# AV-DC.net
KiCad netlist of a schematic drawn in EAGLE
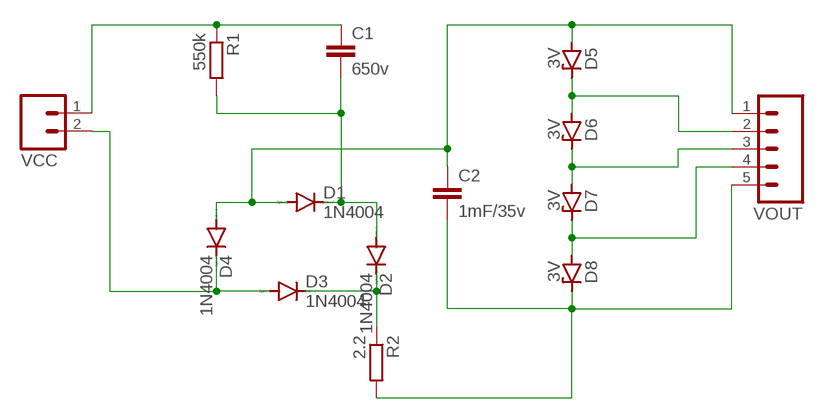
[diagram p0: schematic, sheet 1]

(export (version "E")
  (design (tool "Eeschema 10.0.6"))
  (components
    (comp (ref "C1")
      (value "650v")
      (footprint "eagle-import:C5B3")
      (libsource (lib "eagle-import") (part "C5/3"))
    )
    (comp (ref "C2")
      (value "1mF/35v")
      (footprint "eagle-import:C2.5-2")
      (libsource (lib "eagle-import") (part "C2.5/2"))
    )
    (comp (ref "D1")
      (value "1N4004")
      (footprint "eagle-import:DO41-10")
      (libsource (lib "eagle-import") (part "1N4004"))
    )
    (comp (ref "D2")
      (value "1N4004")
      (footprint "eagle-import:DO41-10")
      (libsource (lib "eagle-import") (part "1N4004"))
    )
    (comp (ref "D3")
      (value "1N4004")
      (footprint "eagle-import:DO41-10")
      (libsource (lib "eagle-import") (part "1N4004"))
    )
    (comp (ref "D4")
      (value "1N4004")
      (footprint "eagle-import:DO41-10")
      (libsource (lib "eagle-import") (part "1N4004"))
    )
    (comp (ref "D5")
      (value "3V")
      (footprint "eagle-import:DO41Z10")
      (libsource (lib "eagle-import") (part "ZENER-DIODEDO41Z10"))
    )
    (comp (ref "D6")
      (value "3V")
      (footprint "eagle-import:DO41Z10")
      (libsource (lib "eagle-import") (part "ZENER-DIODEDO41Z10"))
    )
    (comp (ref "D7")
      (value "3V")
      (footprint "eagle-import:DO41Z10")
      (libsource (lib "eagle-import") (part "ZENER-DIODEDO41Z10"))
    )
    (comp (ref "D8")
      (value "3V")
      (footprint "eagle-import:DO41Z10")
      (libsource (lib "eagle-import") (part "ZENER-DIODEDO41Z10"))
    )
    (comp (ref "R1")
      (value "550k")
      (footprint "eagle-import:0207_10")
      (libsource (lib "eagle-import") (part "R-EU_0207/10"))
    )
    (comp (ref "R2")
      (value "2.2")
      (footprint "eagle-import:0207_10")
      (libsource (lib "eagle-import") (part "R-EU_0207/10"))
    )
    (comp (ref "VCC")
      (value "M02")
      (footprint "eagle-import:02P")
      (libsource (lib "eagle-import") (part "M02"))
    )
    (comp (ref "VOUT")
      (value "M05")
      (footprint "eagle-import:05P")
      (libsource (lib "eagle-import") (part "M05"))
    )
  )
  (nets
    (net (code "1") (name "Net-(C1-Pad1)") (class "Default")
      (node (ref "C1") (pin "1") (pinfunction "1_1") (pintype "passive"))
      (node (ref "R1") (pin "1") (pinfunction "1_1") (pintype "passive"))
      (node (ref "VCC") (pin "1") (pinfunction "1_1") (pintype "passive"))
    )
    (net (code "2") (name "Net-(C1-Pad2)") (class "Default")
      (node (ref "C1") (pin "2") (pinfunction "2_2") (pintype "passive"))
      (node (ref "D1") (pin "C") (pinfunction "C_C") (pintype "passive"))
      (node (ref "D2") (pin "A") (pinfunction "A_A") (pintype "passive"))
      (node (ref "R1") (pin "2") (pinfunction "2_2") (pintype "passive"))
    )
    (net (code "3") (name "Net-(C2-Pad1)") (class "Default")
      (node (ref "C2") (pin "1") (pinfunction "1_1") (pintype "passive"))
      (node (ref "D1") (pin "A") (pinfunction "A_A") (pintype "passive"))
      (node (ref "D4") (pin "A") (pinfunction "A_A") (pintype "passive"))
      (node (ref "D5") (pin "A") (pinfunction "A_A") (pintype "passive"))
      (node (ref "VOUT") (pin "1") (pinfunction "1_1") (pintype "passive"))
    )
    (net (code "4") (name "Net-(C2-Pad2)") (class "Default")
      (node (ref "C2") (pin "2") (pinfunction "2_2") (pintype "passive"))
      (node (ref "D8") (pin "C") (pinfunction "C_C") (pintype "passive"))
      (node (ref "R2") (pin "2") (pinfunction "2_2") (pintype "passive"))
      (node (ref "VOUT") (pin "5") (pinfunction "5_5") (pintype "passive"))
    )
    (net (code "5") (name "Net-(D2-PadC)") (class "Default")
      (node (ref "D2") (pin "C") (pinfunction "C_C") (pintype "passive"))
      (node (ref "D3") (pin "C") (pinfunction "C_C") (pintype "passive"))
      (node (ref "R2") (pin "1") (pinfunction "1_1") (pintype "passive"))
    )
    (net (code "6") (name "Net-(D3-PadA)") (class "Default")
      (node (ref "D3") (pin "A") (pinfunction "A_A") (pintype "passive"))
      (node (ref "D4") (pin "C") (pinfunction "C_C") (pintype "passive"))
      (node (ref "VCC") (pin "2") (pinfunction "2_2") (pintype "passive"))
    )
    (net (code "7") (name "Net-(D5-PadC)") (class "Default")
      (node (ref "D5") (pin "C") (pinfunction "C_C") (pintype "passive"))
      (node (ref "D6") (pin "A") (pinfunction "A_A") (pintype "passive"))
      (node (ref "VOUT") (pin "2") (pinfunction "2_2") (pintype "passive"))
    )
    (net (code "8") (name "Net-(D6-PadC)") (class "Default")
      (node (ref "D6") (pin "C") (pinfunction "C_C") (pintype "passive"))
      (node (ref "D7") (pin "A") (pinfunction "A_A") (pintype "passive"))
      (node (ref "VOUT") (pin "3") (pinfunction "3_3") (pintype "passive"))
    )
    (net (code "9") (name "Net-(D7-PadC)") (class "Default")
      (node (ref "D7") (pin "C") (pinfunction "C_C") (pintype "passive"))
      (node (ref "D8") (pin "A") (pinfunction "A_A") (pintype "passive"))
      (node (ref "VOUT") (pin "4") (pinfunction "4_4") (pintype "passive"))
    )
  )
)
